# AmpSSM2019_230307fab.net
KiCad netlist of a schematic drawn in EAGLE
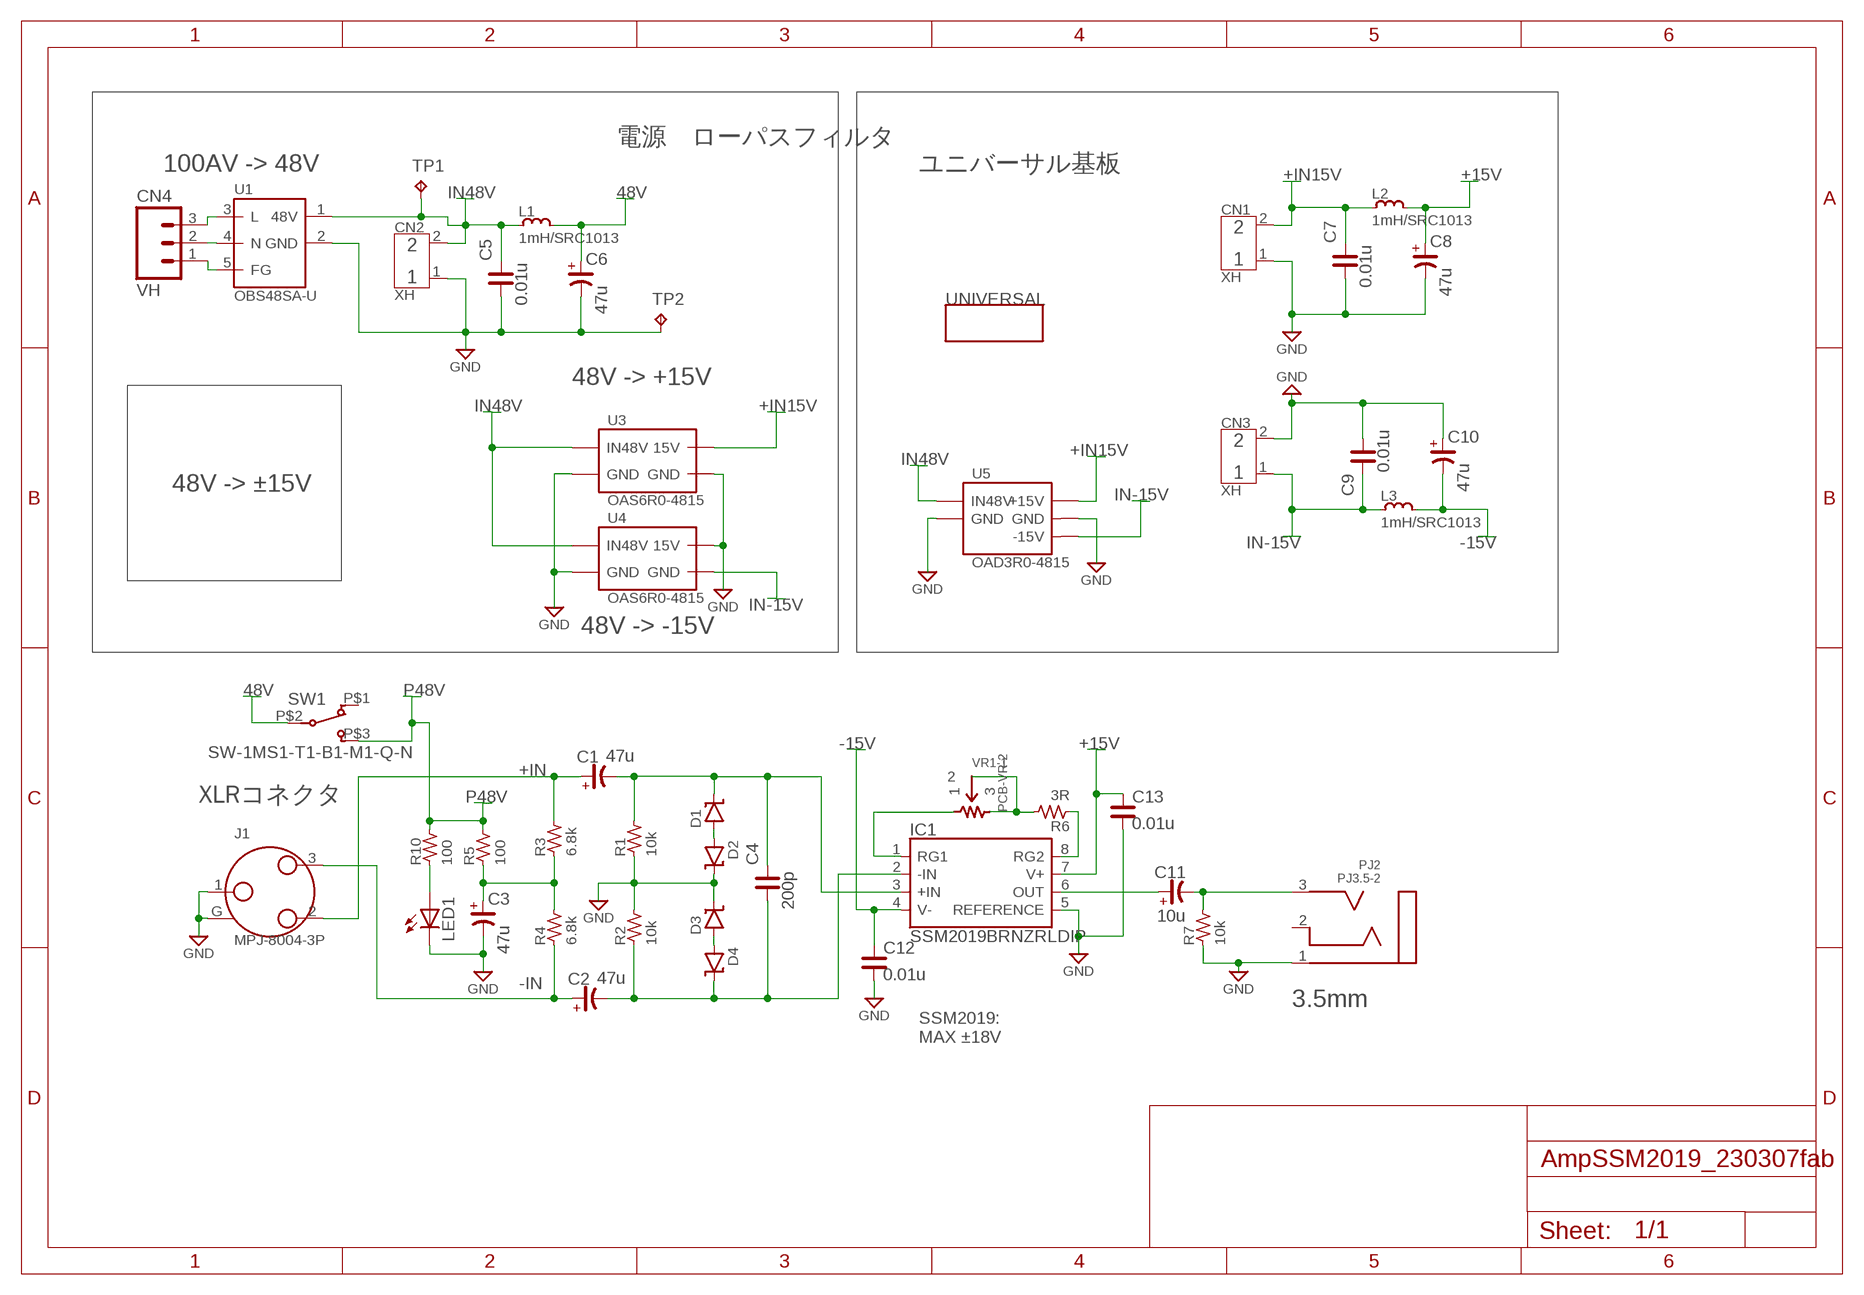
[diagram p0: schematic, sheet 1]

(export (version "E")
  (design (tool "Eeschema 10.0.6"))
  (components
    (comp (ref "C1")
      (value "47u")
      (footprint "eagle-import:CE-025X065")
      (libsource (lib "eagle-import") (part "CP_C025X065"))
    )
    (comp (ref "C2")
      (value "47u")
      (footprint "eagle-import:CE-025X065")
      (libsource (lib "eagle-import") (part "CP_C025X065"))
    )
    (comp (ref "C3")
      (value "47u")
      (footprint "eagle-import:CE-025X065")
      (libsource (lib "eagle-import") (part "CP_C025X065"))
    )
    (comp (ref "C4")
      (value "200p")
      (footprint "eagle-import:C0603")
      (libsource (lib "eagle-import") (part "C_0603"))
    )
    (comp (ref "C5")
      (value "0.01u")
      (footprint "eagle-import:C0603")
      (libsource (lib "eagle-import") (part "C_0603"))
    )
    (comp (ref "C6")
      (value "47u")
      (footprint "eagle-import:CE-025X065")
      (libsource (lib "eagle-import") (part "CP_C025X065"))
    )
    (comp (ref "C7")
      (value "0.01u")
      (footprint "eagle-import:C0603")
      (libsource (lib "eagle-import") (part "C_0603"))
    )
    (comp (ref "C8")
      (value "47u")
      (footprint "eagle-import:CE-025X065")
      (libsource (lib "eagle-import") (part "CP_C025X065"))
    )
    (comp (ref "C9")
      (value "0.01u")
      (footprint "eagle-import:C0603")
      (libsource (lib "eagle-import") (part "C_0603"))
    )
    (comp (ref "C10")
      (value "47u")
      (footprint "eagle-import:CE-025X065")
      (libsource (lib "eagle-import") (part "CP_C025X065"))
    )
    (comp (ref "C11")
      (value "10u")
      (footprint "eagle-import:CE-025X065")
      (libsource (lib "eagle-import") (part "CP_C025X065"))
    )
    (comp (ref "C12")
      (value "0.01u")
      (footprint "eagle-import:C0603")
      (libsource (lib "eagle-import") (part "C_0603"))
    )
    (comp (ref "C13")
      (value "0.01u")
      (footprint "eagle-import:C0603")
      (libsource (lib "eagle-import") (part "C_0603"))
    )
    (comp (ref "CN1")
      (value "XH")
      (footprint "eagle-import:B2B-XH-A")
      (libsource (lib "eagle-import") (part "CN-B2B-XH-A"))
    )
    (comp (ref "CN2")
      (value "XH")
      (footprint "eagle-import:B2B-XH-A")
      (libsource (lib "eagle-import") (part "CN-B2B-XH-A"))
    )
    (comp (ref "CN3")
      (value "XH")
      (footprint "eagle-import:B2B-XH-A")
      (libsource (lib "eagle-import") (part "CN-B2B-XH-A"))
    )
    (comp (ref "CN4")
      (value "VH")
      (footprint "eagle-import:VH3")
      (libsource (lib "eagle-import") (part "M03VH"))
    )
    (comp (ref "D1")
      (value "ZD323")
      (footprint "eagle-import:SOD-323")
      (libsource (lib "eagle-import") (part "ZD323"))
    )
    (comp (ref "D2")
      (value "ZD323")
      (footprint "eagle-import:SOD-323")
      (libsource (lib "eagle-import") (part "ZD323"))
    )
    (comp (ref "D3")
      (value "ZD323")
      (footprint "eagle-import:SOD-323")
      (libsource (lib "eagle-import") (part "ZD323"))
    )
    (comp (ref "D4")
      (value "ZD323")
      (footprint "eagle-import:SOD-323")
      (libsource (lib "eagle-import") (part "ZD323"))
    )
    (comp (ref "IC1")
      (value "SSM2019BRNZRLDIP")
      (footprint "eagle-import:DIL08")
      (libsource (lib "eagle-import") (part "SSM2019BRNZRLDIP"))
    )
    (comp (ref "J1")
      (value "MPJ-8004-3P")
      (footprint "eagle-import:MPJ-8004-3P")
      (libsource (lib "eagle-import") (part "MPJ-8004-3P"))
    )
    (comp (ref "L1")
      (value "1mH/SRC1013")
      (footprint "eagle-import:L13X15")
      (libsource (lib "eagle-import") (part "L_13X15"))
    )
    (comp (ref "L2")
      (value "1mH/SRC1013")
      (footprint "eagle-import:L13X15")
      (libsource (lib "eagle-import") (part "L_13X15"))
    )
    (comp (ref "L3")
      (value "1mH/SRC1013")
      (footprint "eagle-import:L13X15")
      (libsource (lib "eagle-import") (part "L_13X15"))
    )
    (comp (ref "LED1")
      (value "LED3MM")
      (footprint "eagle-import:LED3MM")
      (libsource (lib "eagle-import") (part "LED3MM"))
    )
    (comp (ref "PJ2")
      (value "PJ3.5-2")
      (footprint "eagle-import:PJ3.5-2")
      (libsource (lib "eagle-import") (part "PJ3.5-2"))
    )
    (comp (ref "R1")
      (value "10k")
      (footprint "eagle-import:R0603")
      (libsource (lib "eagle-import") (part "R_0603"))
    )
    (comp (ref "R2")
      (value "10k")
      (footprint "eagle-import:R0603")
      (libsource (lib "eagle-import") (part "R_0603"))
    )
    (comp (ref "R3")
      (value "6.8k")
      (footprint "eagle-import:R0603")
      (libsource (lib "eagle-import") (part "R_0603"))
    )
    (comp (ref "R4")
      (value "6.8k")
      (footprint "eagle-import:R0603")
      (libsource (lib "eagle-import") (part "R_0603"))
    )
    (comp (ref "R5")
      (value "100")
      (footprint "eagle-import:R0603")
      (libsource (lib "eagle-import") (part "R_0603"))
    )
    (comp (ref "R6")
      (value "3R")
      (footprint "eagle-import:R0603")
      (libsource (lib "eagle-import") (part "R_0603"))
    )
    (comp (ref "R7")
      (value "10k")
      (footprint "eagle-import:R0603")
      (libsource (lib "eagle-import") (part "R_0603"))
    )
    (comp (ref "R10")
      (value "100")
      (footprint "eagle-import:R0603")
      (libsource (lib "eagle-import") (part "R_0603"))
    )
    (comp (ref "SW1")
      (value "SW-1MS1-T1-B1-M1-Q-N")
      (footprint "eagle-import:1MS1-T1-B1-M1-Q-N")
      (libsource (lib "eagle-import") (part "SW-1MS1-T1-B1-M1-Q-N"))
    )
    (comp (ref "TP1")
      (value "TPPAD1-13")
      (footprint "eagle-import:P1-13")
      (libsource (lib "eagle-import") (part "TPPAD1-13"))
    )
    (comp (ref "TP2")
      (value "TPPAD1-13")
      (footprint "eagle-import:P1-13")
      (libsource (lib "eagle-import") (part "TPPAD1-13"))
    )
    (comp (ref "U1")
      (value "OBS48SA-U")
      (footprint "eagle-import:OBS48SA-U")
      (libsource (lib "eagle-import") (part "OBS48SA-U"))
    )
    (comp (ref "U2")
      (value "UNIVERSAL10X10")
      (footprint "eagle-import:UNIVERSAL10X10")
      (libsource (lib "eagle-import") (part "UNIVERSAL10X10"))
    )
    (comp (ref "U3")
      (value "OAS6R0-4815")
      (footprint "eagle-import:OAS6R0-4815")
      (libsource (lib "eagle-import") (part "OAS6R0-4815"))
    )
    (comp (ref "U4")
      (value "OAS6R0-4815")
      (footprint "eagle-import:OAS6R0-4815")
      (libsource (lib "eagle-import") (part "OAS6R0-4815"))
    )
    (comp (ref "U5")
      (value "OAD3R0-4815")
      (footprint "eagle-import:OAD3R0-4815")
      (libsource (lib "eagle-import") (part "OAD3R0-4815"))
    )
    (comp (ref "VR1")
      (value "PCB-VR-2")
      (footprint "eagle-import:PCB-VR-2")
      (libsource (lib "eagle-import") (part "PCB-VR-2"))
    )
  )
  (nets
    (net (code "1") (name "/+15V") (class "Default")
      (node (ref "C13") (pin "2") (pinfunction "2_2") (pintype "passive"))
      (node (ref "C8") (pin "+") (pinfunction "+_+") (pintype "passive"))
      (node (ref "IC1") (pin "7") (pinfunction "V+_7") (pintype "bidirectional"))
      (node (ref "L2") (pin "2") (pinfunction "2_2") (pintype "passive"))
    )
    (net (code "2") (name "/+IN") (class "Default")
      (node (ref "C1") (pin "+") (pinfunction "+_+") (pintype "passive"))
      (node (ref "J1") (pin "2") (pinfunction "2_2") (pintype "bidirectional"))
      (node (ref "R3") (pin "2") (pinfunction "2_2") (pintype "passive"))
    )
    (net (code "3") (name "/+IN15V") (class "Default")
      (node (ref "C7") (pin "2") (pinfunction "2_2") (pintype "passive"))
      (node (ref "CN1") (pin "2") (pinfunction "2_2") (pintype "passive"))
      (node (ref "L2") (pin "1") (pinfunction "1_1") (pintype "passive"))
      (node (ref "U3") (pin "V_OUT") (pinfunction "15V_V_OUT") (pintype "bidirectional"))
      (node (ref "U5") (pin "V+_OUT") (pinfunction "+15V_V+_OUT") (pintype "bidirectional"))
    )
    (net (code "4") (name "/-15V") (class "Default")
      (node (ref "C10") (pin "-") (pinfunction "-_-") (pintype "passive"))
      (node (ref "C12") (pin "2") (pinfunction "2_2") (pintype "passive"))
      (node (ref "IC1") (pin "4") (pinfunction "V-_4") (pintype "bidirectional"))
      (node (ref "L3") (pin "2") (pinfunction "2_2") (pintype "passive"))
    )
    (net (code "5") (name "/-IN") (class "Default")
      (node (ref "C2") (pin "+") (pinfunction "+_+") (pintype "passive"))
      (node (ref "J1") (pin "3") (pinfunction "3_3") (pintype "bidirectional"))
      (node (ref "R4") (pin "1") (pinfunction "1_1") (pintype "passive"))
    )
    (net (code "6") (name "/48V") (class "Default")
      (node (ref "C6") (pin "+") (pinfunction "+_+") (pintype "passive"))
      (node (ref "L1") (pin "2") (pinfunction "2_2") (pintype "passive"))
      (node (ref "SW1") (pin "P$2") (pinfunction "P_P$2") (pintype "passive"))
    )
    (net (code "7") (name "/IN-15V") (class "Default")
      (node (ref "C9") (pin "2") (pinfunction "2_2") (pintype "passive"))
      (node (ref "CN3") (pin "1") (pinfunction "1_1") (pintype "passive"))
      (node (ref "L3") (pin "1") (pinfunction "1_1") (pintype "passive"))
      (node (ref "U4") (pin "G_OUT") (pinfunction "GND_G_OUT") (pintype "bidirectional"))
      (node (ref "U5") (pin "V-_OUT") (pinfunction "-15V_V-_OUT") (pintype "bidirectional"))
    )
    (net (code "8") (name "/IN48V") (class "Default")
      (node (ref "C5") (pin "2") (pinfunction "2_2") (pintype "passive"))
      (node (ref "CN2") (pin "2") (pinfunction "2_2") (pintype "passive"))
      (node (ref "L1") (pin "1") (pinfunction "1_1") (pintype "passive"))
      (node (ref "TP1") (pin "TP") (pinfunction "TP_TP") (pintype "input"))
      (node (ref "U1") (pin "1") (pinfunction "48V_1") (pintype "bidirectional"))
      (node (ref "U3") (pin "VIN") (pinfunction "IN48V_VIN") (pintype "bidirectional"))
      (node (ref "U4") (pin "VIN") (pinfunction "IN48V_VIN") (pintype "bidirectional"))
      (node (ref "U5") (pin "VIN") (pinfunction "IN48V_VIN") (pintype "bidirectional"))
    )
    (net (code "9") (name "/P48V") (class "Default")
      (node (ref "R10") (pin "2") (pinfunction "2_2") (pintype "passive"))
      (node (ref "R5") (pin "2") (pinfunction "2_2") (pintype "passive"))
      (node (ref "SW1") (pin "P$3") (pinfunction "S_P$3") (pintype "passive"))
    )
    (net (code "10") (name "G") (class "Default")
      (node (ref "C10") (pin "+") (pinfunction "+_+") (pintype "passive"))
      (node (ref "C12") (pin "1") (pinfunction "1_1") (pintype "passive"))
      (node (ref "C13") (pin "1") (pinfunction "1_1") (pintype "passive"))
      (node (ref "C3") (pin "-") (pinfunction "-_-") (pintype "passive"))
      (node (ref "C5") (pin "1") (pinfunction "1_1") (pintype "passive"))
      (node (ref "C6") (pin "-") (pinfunction "-_-") (pintype "passive"))
      (node (ref "C7") (pin "1") (pinfunction "1_1") (pintype "passive"))
      (node (ref "C8") (pin "-") (pinfunction "-_-") (pintype "passive"))
      (node (ref "C9") (pin "1") (pinfunction "1_1") (pintype "passive"))
      (node (ref "CN1") (pin "1") (pinfunction "1_1") (pintype "passive"))
      (node (ref "CN2") (pin "1") (pinfunction "1_1") (pintype "passive"))
      (node (ref "CN3") (pin "2") (pinfunction "2_2") (pintype "passive"))
      (node (ref "D2") (pin "K") (pinfunction "C_K") (pintype "passive"))
      (node (ref "D3") (pin "K") (pinfunction "C_K") (pintype "passive"))
      (node (ref "IC1") (pin "5") (pinfunction "REFERENCE_5") (pintype "bidirectional"))
      (node (ref "J1") (pin "1") (pinfunction "1_1") (pintype "bidirectional"))
      (node (ref "J1") (pin "G") (pinfunction "G_G") (pintype "bidirectional"))
      (node (ref "LED1") (pin "K") (pinfunction "C_K") (pintype "passive"))
      (node (ref "PJ2") (pin "1") (pinfunction "S_1") (pintype "passive"))
      (node (ref "R1") (pin "1") (pinfunction "1_1") (pintype "passive"))
      (node (ref "R2") (pin "2") (pinfunction "2_2") (pintype "passive"))
      (node (ref "R7") (pin "1") (pinfunction "1_1") (pintype "passive"))
      (node (ref "TP2") (pin "TP") (pinfunction "TP_TP") (pintype "input"))
      (node (ref "U1") (pin "2") (pinfunction "GND_2") (pintype "bidirectional"))
      (node (ref "U3") (pin "G_IN") (pinfunction "GND_G_IN") (pintype "bidirectional"))
      (node (ref "U3") (pin "G_OUT") (pinfunction "GND_G_OUT") (pintype "bidirectional"))
      (node (ref "U4") (pin "G_IN") (pinfunction "GND_G_IN") (pintype "bidirectional"))
      (node (ref "U4") (pin "V_OUT") (pinfunction "15V_V_OUT") (pintype "bidirectional"))
      (node (ref "U5") (pin "G_IN") (pinfunction "GND_G_IN") (pintype "bidirectional"))
      (node (ref "U5") (pin "G_OUT") (pinfunction "GND_G_OUT") (pintype "bidirectional"))
    )
    (net (code "11") (name "Net-(C3-Pad+)") (class "Default")
      (node (ref "C3") (pin "+") (pinfunction "+_+") (pintype "passive"))
      (node (ref "R3") (pin "1") (pinfunction "1_1") (pintype "passive"))
      (node (ref "R4") (pin "2") (pinfunction "2_2") (pintype "passive"))
      (node (ref "R5") (pin "1") (pinfunction "1_1") (pintype "passive"))
    )
    (net (code "12") (name "Net-(D1-C)") (class "Default")
      (node (ref "C1") (pin "-") (pinfunction "-_-") (pintype "passive"))
      (node (ref "C4") (pin "2") (pinfunction "2_2") (pintype "passive"))
      (node (ref "D1") (pin "K") (pinfunction "C_K") (pintype "passive"))
      (node (ref "IC1") (pin "3") (pinfunction "+IN_3") (pintype "bidirectional"))
      (node (ref "R1") (pin "2") (pinfunction "2_2") (pintype "passive"))
    )
    (net (code "13") (name "Net-(D1-PadA)") (class "Default")
      (node (ref "D1") (pin "A") (pinfunction "A_A") (pintype "passive"))
      (node (ref "D2") (pin "A") (pinfunction "A_A") (pintype "passive"))
    )
    (net (code "14") (name "Net-(D3-PadA)") (class "Default")
      (node (ref "D3") (pin "A") (pinfunction "A_A") (pintype "passive"))
      (node (ref "D4") (pin "A") (pinfunction "A_A") (pintype "passive"))
    )
    (net (code "15") (name "Net-(D4-C)") (class "Default")
      (node (ref "C2") (pin "-") (pinfunction "-_-") (pintype "passive"))
      (node (ref "C4") (pin "1") (pinfunction "1_1") (pintype "passive"))
      (node (ref "D4") (pin "K") (pinfunction "C_K") (pintype "passive"))
      (node (ref "IC1") (pin "2") (pinfunction "-IN_2") (pintype "bidirectional"))
      (node (ref "R2") (pin "1") (pinfunction "1_1") (pintype "passive"))
    )
    (net (code "16") (name "Net-(IC1-OUT)") (class "Default")
      (node (ref "C11") (pin "+") (pinfunction "+_+") (pintype "passive"))
      (node (ref "IC1") (pin "6") (pinfunction "OUT_6") (pintype "bidirectional"))
    )
    (net (code "17") (name "Net-(IC1-RG1)") (class "Default")
      (node (ref "IC1") (pin "1") (pinfunction "RG1_1") (pintype "bidirectional"))
      (node (ref "VR1") (pin "3") (pinfunction "1_3") (pintype "passive"))
    )
    (net (code "18") (name "Net-(IC1-RG2)") (class "Default")
      (node (ref "IC1") (pin "8") (pinfunction "RG2_8") (pintype "bidirectional"))
      (node (ref "R6") (pin "1") (pinfunction "1_1") (pintype "passive"))
    )
    (net (code "19") (name "Net-(LED1-PadA)") (class "Default")
      (node (ref "LED1") (pin "A") (pinfunction "A_A") (pintype "passive"))
      (node (ref "R10") (pin "1") (pinfunction "1_1") (pintype "passive"))
    )
    (net (code "20") (name "Net-(PJ2-TIP)") (class "Default")
      (node (ref "C11") (pin "-") (pinfunction "-_-") (pintype "passive"))
      (node (ref "PJ2") (pin "3") (pinfunction "TIP_3") (pintype "passive"))
      (node (ref "R7") (pin "2") (pinfunction "2_2") (pintype "passive"))
    )
    (net (code "21") (name "Net-(U1-FG)") (class "Default")
      (node (ref "CN4") (pin "1") (pinfunction "1_1") (pintype "passive"))
      (node (ref "U1") (pin "5") (pinfunction "FG_5") (pintype "bidirectional"))
    )
    (net (code "22") (name "Net-(U1-L)") (class "Default")
      (node (ref "CN4") (pin "3") (pinfunction "3_3") (pintype "passive"))
      (node (ref "U1") (pin "3") (pinfunction "L_3") (pintype "bidirectional"))
    )
    (net (code "23") (name "Net-(U1-N)") (class "Default")
      (node (ref "CN4") (pin "2") (pinfunction "2_2") (pintype "passive"))
      (node (ref "U1") (pin "4") (pinfunction "N_4") (pintype "bidirectional"))
    )
    (net (code "24") (name "Net-(VR1A-3)") (class "Default")
      (node (ref "R6") (pin "2") (pinfunction "2_2") (pintype "passive"))
      (node (ref "VR1") (pin "1") (pinfunction "3_1") (pintype "passive"))
      (node (ref "VR1") (pin "2") (pinfunction "2_2") (pintype "passive"))
    )
    (net (code "25") (name "unconnected-(PJ2-RING-Pad2)") (class "Default")
      (node (ref "PJ2") (pin "2") (pinfunction "RING_2") (pintype "passive"))
    )
    (net (code "26") (name "unconnected-(SW1-O-PadP$1)") (class "Default")
      (node (ref "SW1") (pin "P$1") (pinfunction "O_P$1") (pintype "passive"))
    )
  )
)
